# 555-indicator-sheet.net
KiCad netlist of a schematic drawn in Altium Designer
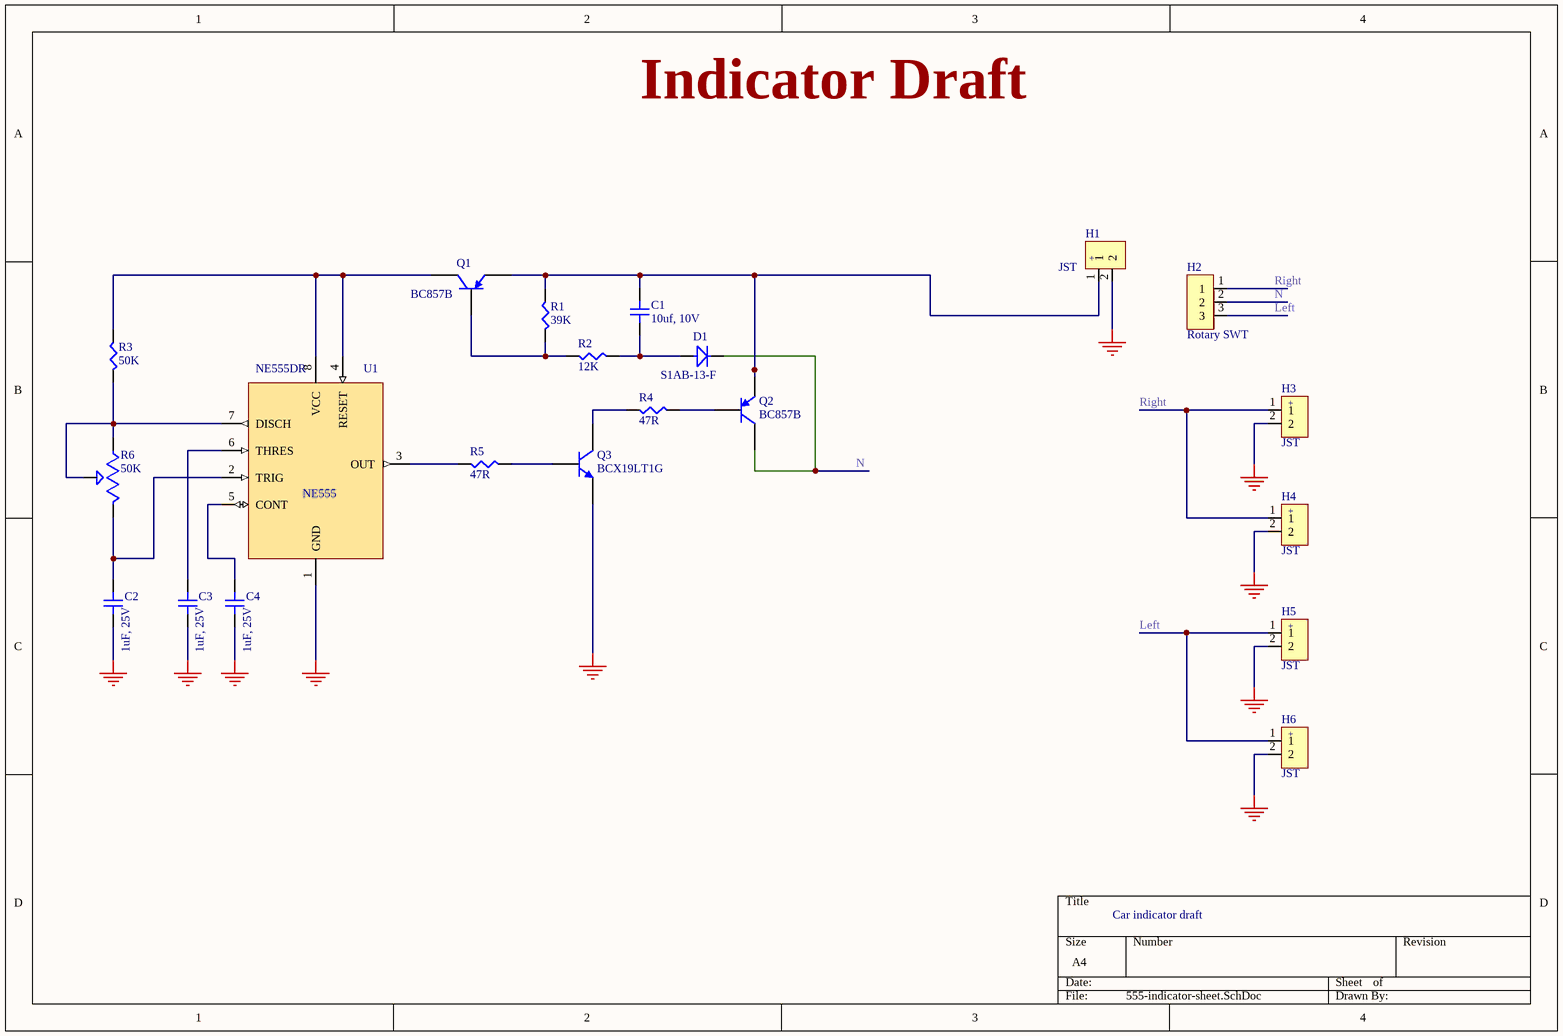
[diagram p0: 555-indicator-sheet.SchDoc]

(export (version "E")
  (design (tool "Eeschema 10.0.6"))
  (components
    (comp (ref "C1")
      (value "10uf, 10V")
      (footprint "CAPC2012X140N")
      (description "CAP CER 10UF 10V X5R 0805")
      (fields
        (field (name "MANUFACTURER") "Samsung")
        (field (name "MANUFACTURER PART NUMBER") "CL21A106KPFNNNE")
      )
      (libsource (lib "555-indicator-Schlib") (part "CL21A106KPFNNNE"))
    )
    (comp (ref "C2")
      (value "1uF, 25V")
      (footprint "CAPC2012X140N")
      (description "CAP CER 1UF 25V X7R 0805")
      (fields
        (field (name "MANUFACTURER") "Samsung")
        (field (name "MANUFACTURER PART NUMBER") "CL21B105KAFNNNE")
      )
      (libsource (lib "555-indicator-Schlib") (part "CL21B105KAFNNNE"))
    )
    (comp (ref "C3")
      (value "1uF, 25V")
      (footprint "CAPC2012X140N")
      (description "CAP CER 1UF 25V X7R 0805")
      (fields
        (field (name "MANUFACTURER") "Samsung")
        (field (name "MANUFACTURER PART NUMBER") "CL21B105KAFNNNE")
      )
      (libsource (lib "555-indicator-Schlib") (part "CL21B105KAFNNNE"))
    )
    (comp (ref "C4")
      (value "1uF, 25V")
      (footprint "CAPC2012X140N")
      (description "CAP CER 1UF 25V X7R 0805")
      (fields
        (field (name "MANUFACTURER") "Samsung")
        (field (name "MANUFACTURER PART NUMBER") "CL21B105KAFNNNE")
      )
      (libsource (lib "555-indicator-Schlib") (part "CL21B105KAFNNNE"))
    )
    (comp (ref "D1")
      (value "S1AB-13-F")
      (footprint "FP-SMB-MFG")
      (description "DIODE GEN PURP 50V 1A DO214AC")
      (fields (field (name "MANUFACTURER") "Diodes") (field (name "LCSC PART NO") "C519094"))
      (libsource (lib "555-indicator-Schlib") (part "S1AB-13-F"))
    )
    (comp (ref "H1")
      (value "JST")
      (footprint "FP-B2B-XH-A_LF_SN-MFG")
      (description "CONN HEADER VERT 2POS 2.5MM")
      (fields
        (field (name "MANUFACTURER PART NUMBER") "B2B-XH-A(LF)(SN)")
        (field (name "LCSC PART NO") "C158012")
      )
      (libsource (lib "") (part "B2B-XH-A(LF)(SN)_1"))
    )
    (comp (ref "H2")
      (value "Rotary SWT")
      (footprint "JST_B3B-XH-A")
      (description "CONN HEADER VERT 3POS 2.5MM")
      (fields
        (field (name "MANUFACTURER") "JST")
        (field (name "MANUFACTURER PART NUMBER") "B3B-XH-A(LF)(SN)")
      )
      (libsource (lib "555-indicator-Schlib") (part "B3B-XH-A(LF)(SN)"))
    )
    (comp (ref "H3")
      (value "JST")
      (footprint "FP-B2B-XH-A_LF_SN-MFG")
      (description "CONN HEADER VERT 2POS 2.5MM")
      (fields
        (field (name "MANUFACTURER PART NUMBER") "B2B-XH-A(LF)(SN)")
        (field (name "LCSC PART NO") "C158012")
      )
      (libsource (lib "555-indicator-Schlib") (part "B2B-XH-A(LF)(SN)"))
    )
    (comp (ref "H4")
      (value "JST")
      (footprint "FP-B2B-XH-A_LF_SN-MFG")
      (description "CONN HEADER VERT 2POS 2.5MM")
      (fields
        (field (name "MANUFACTURER PART NUMBER") "B2B-XH-A(LF)(SN)")
        (field (name "LCSC PART NO") "C158012")
      )
      (libsource (lib "555-indicator-Schlib") (part "B2B-XH-A(LF)(SN)"))
    )
    (comp (ref "H5")
      (value "JST")
      (footprint "FP-B2B-XH-A_LF_SN-MFG")
      (description "CONN HEADER VERT 2POS 2.5MM")
      (fields
        (field (name "MANUFACTURER PART NUMBER") "B2B-XH-A(LF)(SN)")
        (field (name "LCSC PART NO") "C158012")
      )
      (libsource (lib "555-indicator-Schlib") (part "B2B-XH-A(LF)(SN)"))
    )
    (comp (ref "H6")
      (value "JST")
      (footprint "FP-B2B-XH-A_LF_SN-MFG")
      (description "CONN HEADER VERT 2POS 2.5MM")
      (fields
        (field (name "MANUFACTURER PART NUMBER") "B2B-XH-A(LF)(SN)")
        (field (name "LCSC PART NO") "C158012")
      )
      (libsource (lib "555-indicator-Schlib") (part "B2B-XH-A(LF)(SN)"))
    )
    (comp (ref "Q1")
      (value "BC857B")
      (footprint "PNP_BC857B,235")
      (description "BJT SOT-23 45V 100MA")
      (fields (field (name "MANUFACTURER") "Infineon") (field (name "LCSC PART NO") "C181146"))
      (libsource (lib "555-indicator-Schlib") (part "BC857B"))
    )
    (comp (ref "Q2")
      (value "BC857B")
      (footprint "PNP_BC857B,235")
      (description "BJT SOT-23 45V 100MA")
      (fields (field (name "MANUFACTURER") "Infineon") (field (name "LCSC PART NO") "C181146"))
      (libsource (lib "555-indicator-Schlib") (part "BC857B"))
    )
    (comp (ref "Q3")
      (value "BCX19LT1G")
      (footprint "NPN_BCX19LT1G")
      (description "TRANS NPN 45V 0.5A SOT23-3")
      (fields (field (name "MANUFACTURER") "ON Semiconductor") (field (name "LCSC PART NO") "C232541"))
      (libsource (lib "555-indicator-Schlib") (part "BCX19LT1G"))
    )
    (comp (ref "R1")
      (value "39K")
      (footprint "RESC3116X65N")
      (description "Res SMD 39K Ohm 0.1% 1/4W 0805")
      (fields
        (field (name "MANUFACTURER") "Panasonic")
        (field (name "MANUFACTURER PART NUMBER") "ERJ-PB6B3902V")
      )
      (libsource (lib "555-indicator-Schlib") (part "ERJ-PB6B3902V"))
    )
    (comp (ref "R2")
      (value "12K")
      (footprint "RESC3116X65N")
      (description "RES SMD 12K OHM 0.1% 1/4W 0805")
      (fields
        (field (name "MANUFACTURER") "Panasonic")
        (field (name "MANUFACTURER PART NUMBER") "ERJPB6B1202V")
      )
      (libsource (lib "555-indicator-Schlib") (part "ERJPB6B1202V"))
    )
    (comp (ref "R3")
      (value "50K")
      (footprint "RESC3116X65N")
      (description "RES SMD 50K OHM 0.1% 1/4W 1206")
      (fields
        (field (name "MANUFACTURER") "Yageo")
        (field (name "MANUFACTURER PART NUMBER") "RT1206BRD0750KL")
      )
      (libsource (lib "555-indicator-Schlib") (part "RT1206BRD0750KL"))
    )
    (comp (ref "R4")
      (value "47R")
      (footprint "RESC3116X65N")
      (description "RES 47 OHM 5% 1/4W 0805")
      (fields
        (field (name "MANUFACTURER") "Stackpole Electronics")
        (field (name "MANUFACTURER PART NUMBER") "RPC0805JT47R0")
      )
      (libsource (lib "555-indicator-Schlib") (part "RPC0805JT47R0"))
    )
    (comp (ref "R5")
      (value "47R")
      (footprint "RESC3116X65N")
      (description "RES 47 OHM 5% 1/4W 0805")
      (fields
        (field (name "MANUFACTURER") "Stackpole Electronics")
        (field (name "MANUFACTURER PART NUMBER") "RPC0805JT47R0")
      )
      (libsource (lib "555-indicator-Schlib") (part "RPC0805JT47R0"))
    )
    (comp (ref "R6")
      (value "50K")
      (footprint "TRIM_3266W-1-503LF")
      (description "50K OHM 0.25W PC PIN TOP")
      (fields
        (field (name "MANUFACTURER") "Bourns")
        (field (name "MANUFACTURER PART NUMBER") "3266W-1-503LF")
      )
      (libsource (lib "555-indicator-Schlib") (part "3266W-1-503LF (2)"))
    )
    (comp (ref "U1")
      (value "NE555DR")
      (footprint "FP-D0008A-MFG")
      (description "IC OSC SGL TIMER 100KHZ 8-SOIC")
      (fields (field (name "MANUFACTURER") "Texas Instruments") (field (name "LCSC PART NO") "C7593"))
      (libsource (lib "555-indicator-Schlib") (part "NE555DR"))
    )
  )
  (nets
    (net (code "1") (name "/Left") (class "Default")
      (node (ref "H2") (pin "3") (pinfunction "3_3") (pintype "passive"))
      (node (ref "H5") (pin "1") (pinfunction "1_1") (pintype "passive"))
      (node (ref "H6") (pin "1") (pinfunction "1_1") (pintype "passive"))
    )
    (net (code "2") (name "/N") (class "Default")
      (node (ref "D1") (pin "2") (pinfunction "2_2") (pintype "passive"))
      (node (ref "H2") (pin "2") (pinfunction "2_2") (pintype "passive"))
      (node (ref "Q2") (pin "3") (pinfunction "C_3") (pintype "passive"))
    )
    (net (code "3") (name "/Right") (class "Default")
      (node (ref "H2") (pin "1") (pinfunction "1_1") (pintype "passive"))
      (node (ref "H3") (pin "1") (pinfunction "1_1") (pintype "passive"))
      (node (ref "H4") (pin "1") (pinfunction "1_1") (pintype "passive"))
    )
    (net (code "4") (name "GND") (class "Default")
      (node (ref "C2") (pin "2") (pinfunction "2_2") (pintype "passive"))
      (node (ref "C3") (pin "2") (pinfunction "2_2") (pintype "passive"))
      (node (ref "C4") (pin "2") (pinfunction "2_2") (pintype "passive"))
      (node (ref "H1") (pin "2") (pinfunction "2_2") (pintype "passive"))
      (node (ref "H3") (pin "2") (pinfunction "2_2") (pintype "passive"))
      (node (ref "H4") (pin "2") (pinfunction "2_2") (pintype "passive"))
      (node (ref "H5") (pin "2") (pinfunction "2_2") (pintype "passive"))
      (node (ref "H6") (pin "2") (pinfunction "2_2") (pintype "passive"))
      (node (ref "Q3") (pin "2") (pinfunction "E_2") (pintype "passive"))
      (node (ref "U1") (pin "1") (pinfunction "GND_1") (pintype "passive"))
    )
    (net (code "5") (name "Net-(C1-Pad1)") (class "Default")
      (node (ref "C1") (pin "1") (pinfunction "1_1") (pintype "passive"))
      (node (ref "D1") (pin "1") (pinfunction "1_1") (pintype "passive"))
      (node (ref "R2") (pin "2") (pinfunction "2_2") (pintype "passive"))
    )
    (net (code "6") (name "Net-(Q1-B)") (class "Default")
      (node (ref "Q1") (pin "1") (pinfunction "B_1") (pintype "passive"))
      (node (ref "R1") (pin "2") (pinfunction "2_2") (pintype "passive"))
      (node (ref "R2") (pin "1") (pinfunction "1_1") (pintype "passive"))
    )
    (net (code "7") (name "Net-(Q1-C)") (class "Default")
      (node (ref "Q1") (pin "3") (pinfunction "C_3") (pintype "passive"))
      (node (ref "R3") (pin "1") (pinfunction "1_1") (pintype "passive"))
      (node (ref "U1") (pin "4") (pinfunction "RESET_4") (pintype "input"))
      (node (ref "U1") (pin "8") (pinfunction "VCC_8") (pintype "passive"))
    )
    (net (code "8") (name "Net-(Q1-E)") (class "Default")
      (node (ref "C1") (pin "2") (pinfunction "2_2") (pintype "passive"))
      (node (ref "H1") (pin "1") (pinfunction "1_1") (pintype "passive"))
      (node (ref "Q1") (pin "2") (pinfunction "E_2") (pintype "passive"))
      (node (ref "Q2") (pin "2") (pinfunction "E_2") (pintype "passive"))
      (node (ref "R1") (pin "1") (pinfunction "1_1") (pintype "passive"))
    )
    (net (code "9") (name "Net-(Q2-B)") (class "Default")
      (node (ref "Q2") (pin "1") (pinfunction "B_1") (pintype "passive"))
      (node (ref "R4") (pin "2") (pinfunction "2_2") (pintype "passive"))
    )
    (net (code "10") (name "Net-(Q3-B)") (class "Default")
      (node (ref "Q3") (pin "1") (pinfunction "B_1") (pintype "passive"))
      (node (ref "R5") (pin "2") (pinfunction "2_2") (pintype "passive"))
    )
    (net (code "11") (name "Net-(Q3-C)") (class "Default")
      (node (ref "Q3") (pin "3") (pinfunction "C_3") (pintype "passive"))
      (node (ref "R4") (pin "1") (pinfunction "1_1") (pintype "passive"))
    )
    (net (code "12") (name "Net-(R6-CCW)") (class "Default")
      (node (ref "R3") (pin "2") (pinfunction "2_2") (pintype "passive"))
      (node (ref "R6") (pin "1") (pinfunction "CCW_1") (pintype "passive"))
      (node (ref "R6") (pin "2") (pinfunction "WIPER_2") (pintype "passive"))
      (node (ref "U1") (pin "7") (pinfunction "DISCH_7") (pintype "output"))
    )
    (net (code "13") (name "Net-(R6-CW)") (class "Default")
      (node (ref "C2") (pin "1") (pinfunction "1_1") (pintype "passive"))
      (node (ref "R6") (pin "3") (pinfunction "CW_3") (pintype "passive"))
      (node (ref "U1") (pin "2") (pinfunction "TRIG_2") (pintype "input"))
    )
    (net (code "14") (name "Net-(U1-CONT)") (class "Default")
      (node (ref "C4") (pin "1") (pinfunction "1_1") (pintype "passive"))
      (node (ref "U1") (pin "5") (pinfunction "CONT_5") (pintype "bidirectional"))
    )
    (net (code "15") (name "Net-(U1-OUT)") (class "Default")
      (node (ref "R5") (pin "1") (pinfunction "1_1") (pintype "passive"))
      (node (ref "U1") (pin "3") (pinfunction "OUT_3") (pintype "output"))
    )
    (net (code "16") (name "Net-(U1-THRES)") (class "Default")
      (node (ref "C3") (pin "1") (pinfunction "1_1") (pintype "passive"))
      (node (ref "U1") (pin "6") (pinfunction "THRES_6") (pintype "input"))
    )
  )
)
